# zif_breakout.net
KiCad netlist of a schematic drawn in EAGLE
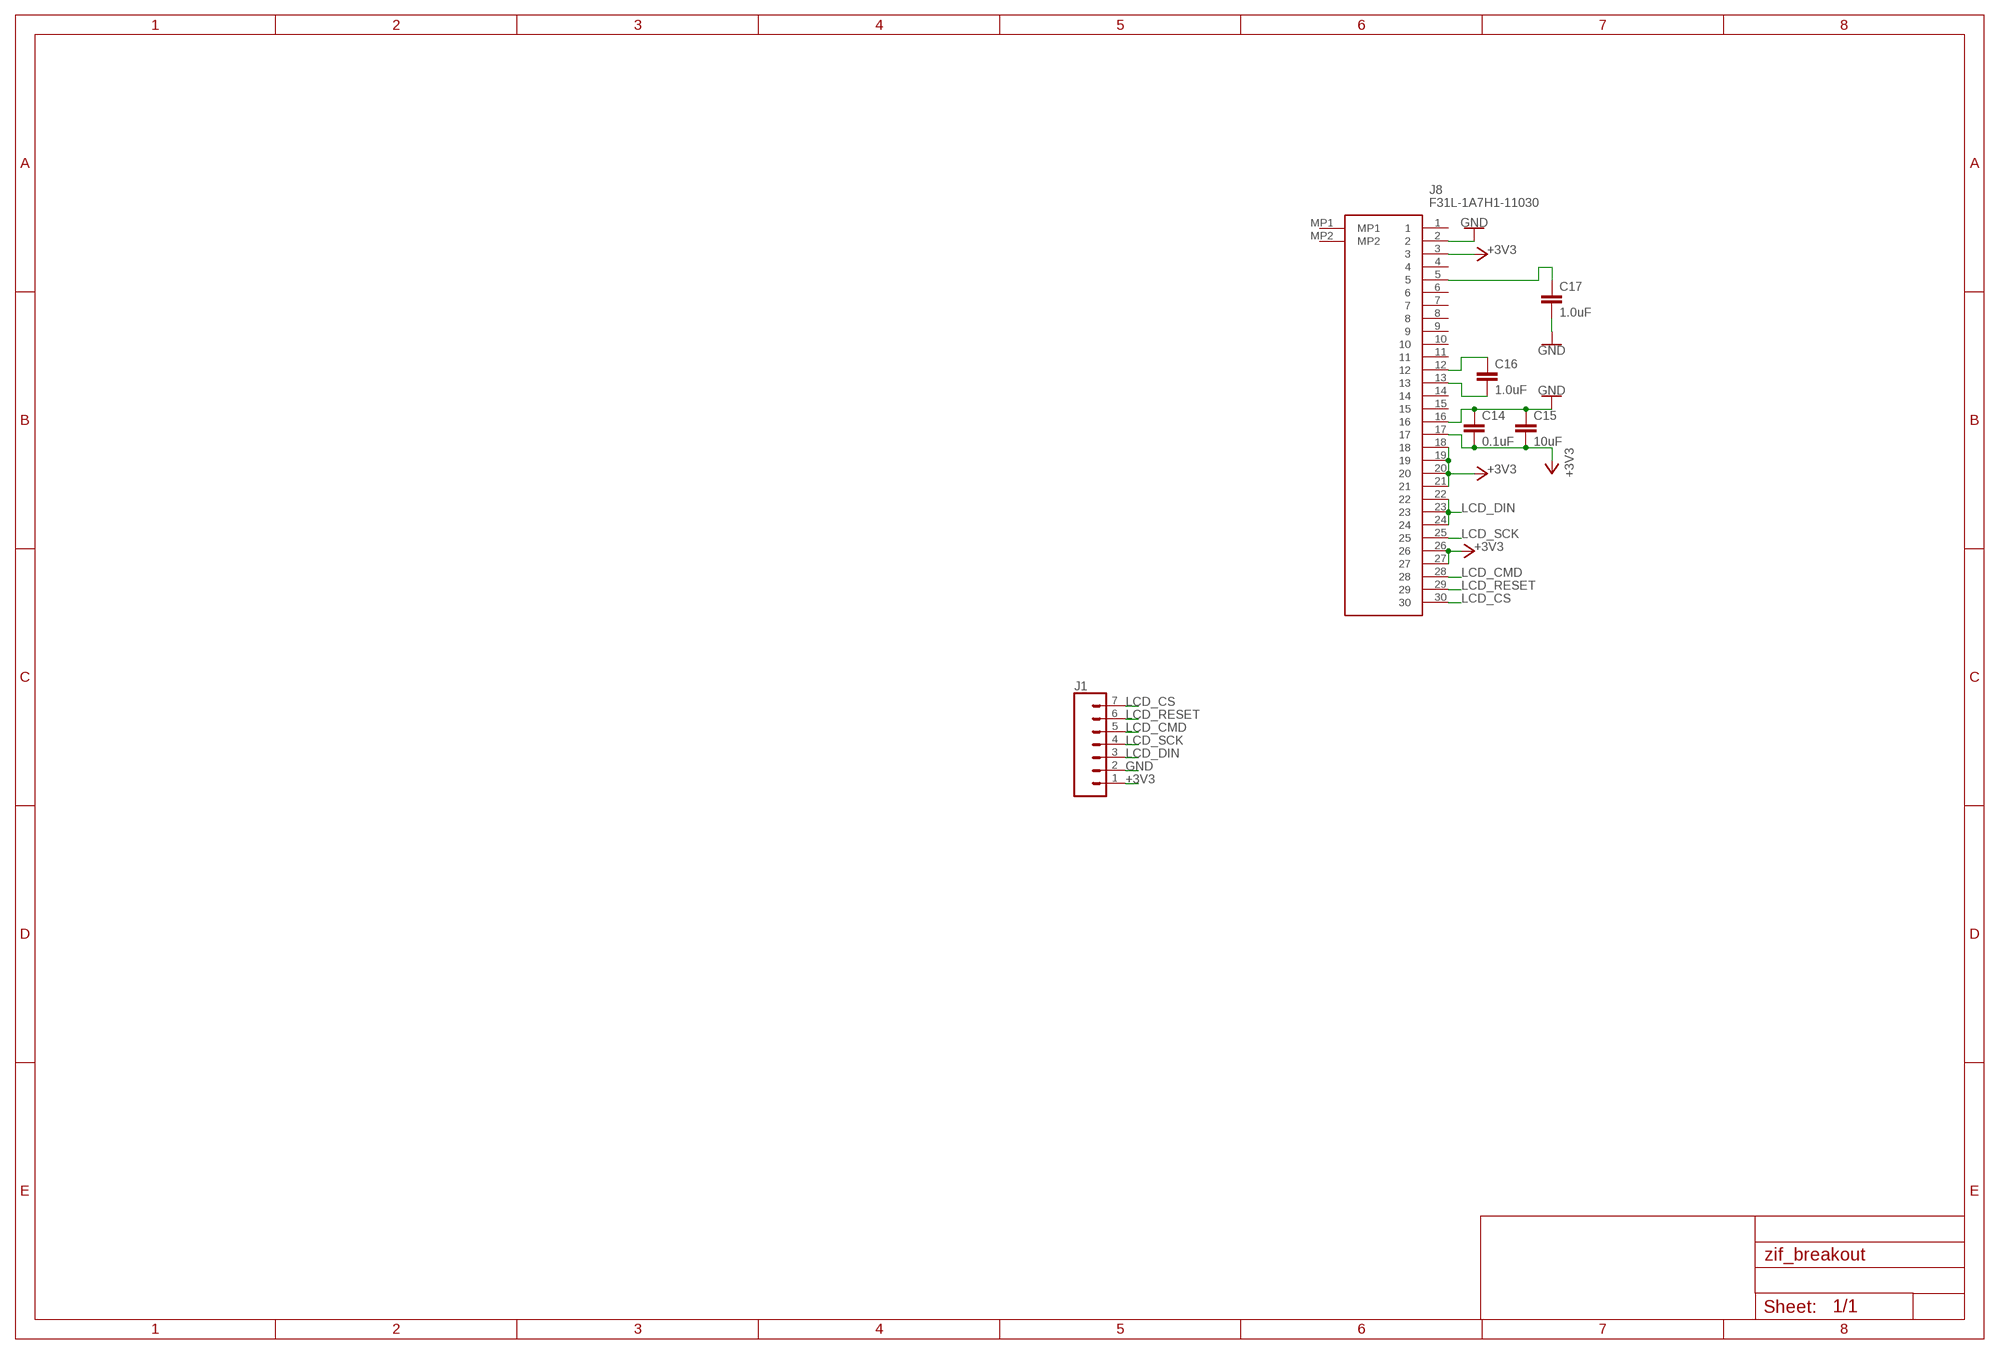
[diagram p0: schematic, sheet 1]

(export (version "E")
  (design (tool "Eeschema 10.0.6"))
  (components
    (comp (ref "C14")
      (value "0.1uF")
      (footprint "eagle-import:0603")
      (libsource (lib "eagle-import") (part "0.1UF-0603-25V-(+80/-20%)"))
    )
    (comp (ref "C15")
      (value "10uF")
      (footprint "eagle-import:0603")
      (libsource (lib "eagle-import") (part "10UF-0603-6.3V-20%"))
    )
    (comp (ref "C16")
      (value "1.0uF")
      (footprint "eagle-import:0603")
      (libsource (lib "eagle-import") (part "1.0UF-0603-16V-10%"))
    )
    (comp (ref "C17")
      (value "1.0uF")
      (footprint "eagle-import:0603")
      (libsource (lib "eagle-import") (part "1.0UF-0603-16V-10%"))
    )
    (comp (ref "J1")
      (value "CONN_07")
      (footprint "eagle-import:1X07")
      (libsource (lib "eagle-import") (part "CONN_07"))
    )
    (comp (ref "J8")
      (value "F31L-1A7H1-11030")
      (footprint "eagle-import:F31L1A7H111030")
      (fields (field (name "MOUSER_PART_NUMBER") "649-F31L-1A7H1-11030"))
      (libsource (lib "eagle-import") (part "F31L-1A7H1-11030"))
    )
  )
  (nets
    (net (code "1") (name "+3V3") (class "Default")
      (node (ref "C14") (pin "2") (pinfunction "2_2") (pintype "passive"))
      (node (ref "C15") (pin "2") (pinfunction "2_2") (pintype "passive"))
      (node (ref "J1") (pin "1") (pinfunction "1_1") (pintype "passive"))
      (node (ref "J8") (pin "17") (pinfunction "17_17") (pintype "bidirectional"))
      (node (ref "J8") (pin "18") (pinfunction "18_18") (pintype "bidirectional"))
      (node (ref "J8") (pin "19") (pinfunction "19_19") (pintype "bidirectional"))
      (node (ref "J8") (pin "20") (pinfunction "20_20") (pintype "bidirectional"))
      (node (ref "J8") (pin "21") (pinfunction "21_21") (pintype "bidirectional"))
      (node (ref "J8") (pin "26") (pinfunction "26_26") (pintype "bidirectional"))
      (node (ref "J8") (pin "27") (pinfunction "27_27") (pintype "bidirectional"))
      (node (ref "J8") (pin "3") (pinfunction "3_3") (pintype "bidirectional"))
    )
    (net (code "2") (name "/LCD_CMD") (class "Default")
      (node (ref "J1") (pin "5") (pinfunction "5_5") (pintype "passive"))
      (node (ref "J8") (pin "28") (pinfunction "28_28") (pintype "bidirectional"))
    )
    (net (code "3") (name "/LCD_CS") (class "Default")
      (node (ref "J1") (pin "7") (pinfunction "7_7") (pintype "passive"))
      (node (ref "J8") (pin "30") (pinfunction "30_30") (pintype "bidirectional"))
    )
    (net (code "4") (name "/LCD_DIN") (class "Default")
      (node (ref "J1") (pin "3") (pinfunction "3_3") (pintype "passive"))
      (node (ref "J8") (pin "22") (pinfunction "22_22") (pintype "bidirectional"))
      (node (ref "J8") (pin "23") (pinfunction "23_23") (pintype "bidirectional"))
      (node (ref "J8") (pin "24") (pinfunction "24_24") (pintype "bidirectional"))
    )
    (net (code "5") (name "/LCD_RESET") (class "Default")
      (node (ref "J1") (pin "6") (pinfunction "6_6") (pintype "passive"))
      (node (ref "J8") (pin "29") (pinfunction "29_29") (pintype "bidirectional"))
    )
    (net (code "6") (name "/LCD_SCK") (class "Default")
      (node (ref "J1") (pin "4") (pinfunction "4_4") (pintype "passive"))
      (node (ref "J8") (pin "25") (pinfunction "25_25") (pintype "bidirectional"))
    )
    (net (code "7") (name "GND") (class "Default")
      (node (ref "C14") (pin "1") (pinfunction "1_1") (pintype "passive"))
      (node (ref "C15") (pin "1") (pinfunction "1_1") (pintype "passive"))
      (node (ref "C17") (pin "2") (pinfunction "2_2") (pintype "passive"))
      (node (ref "J1") (pin "2") (pinfunction "2_2") (pintype "passive"))
      (node (ref "J8") (pin "16") (pinfunction "16_16") (pintype "bidirectional"))
      (node (ref "J8") (pin "2") (pinfunction "2_2") (pintype "bidirectional"))
    )
    (net (code "8") (name "Net-(C16-Pad1)") (class "Default")
      (node (ref "C16") (pin "1") (pinfunction "1_1") (pintype "passive"))
      (node (ref "J8") (pin "12") (pinfunction "12_12") (pintype "bidirectional"))
    )
    (net (code "9") (name "Net-(C16-Pad2)") (class "Default")
      (node (ref "C16") (pin "2") (pinfunction "2_2") (pintype "passive"))
      (node (ref "J8") (pin "13") (pinfunction "13_13") (pintype "bidirectional"))
    )
    (net (code "10") (name "Net-(C17-Pad1)") (class "Default")
      (node (ref "C17") (pin "1") (pinfunction "1_1") (pintype "passive"))
      (node (ref "J8") (pin "5") (pinfunction "5_5") (pintype "bidirectional"))
    )
    (net (code "11") (name "unconnected-(J8-Pad1)") (class "Default")
      (node (ref "J8") (pin "1") (pinfunction "1_1") (pintype "bidirectional"))
    )
    (net (code "12") (name "unconnected-(J8-Pad4)") (class "Default")
      (node (ref "J8") (pin "4") (pinfunction "4_4") (pintype "bidirectional"))
    )
    (net (code "13") (name "unconnected-(J8-Pad6)") (class "Default")
      (node (ref "J8") (pin "6") (pinfunction "6_6") (pintype "bidirectional"))
    )
    (net (code "14") (name "unconnected-(J8-Pad7)") (class "Default")
      (node (ref "J8") (pin "7") (pinfunction "7_7") (pintype "bidirectional"))
    )
    (net (code "15") (name "unconnected-(J8-Pad8)") (class "Default")
      (node (ref "J8") (pin "8") (pinfunction "8_8") (pintype "bidirectional"))
    )
    (net (code "16") (name "unconnected-(J8-Pad9)") (class "Default")
      (node (ref "J8") (pin "9") (pinfunction "9_9") (pintype "bidirectional"))
    )
    (net (code "17") (name "unconnected-(J8-Pad10)") (class "Default")
      (node (ref "J8") (pin "10") (pinfunction "10_10") (pintype "bidirectional"))
    )
    (net (code "18") (name "unconnected-(J8-Pad11)") (class "Default")
      (node (ref "J8") (pin "11") (pinfunction "11_11") (pintype "bidirectional"))
    )
    (net (code "19") (name "unconnected-(J8-Pad14)") (class "Default")
      (node (ref "J8") (pin "14") (pinfunction "14_14") (pintype "bidirectional"))
    )
    (net (code "20") (name "unconnected-(J8-Pad15)") (class "Default")
      (node (ref "J8") (pin "15") (pinfunction "15_15") (pintype "bidirectional"))
    )
    (net (code "21") (name "unconnected-(J8-PadMP1)") (class "Default")
      (node (ref "J8") (pin "MP1") (pinfunction "MP1_MP1") (pintype "bidirectional"))
    )
    (net (code "22") (name "unconnected-(J8-PadMP2)") (class "Default")
      (node (ref "J8") (pin "MP2") (pinfunction "MP2_MP2") (pintype "bidirectional"))
    )
  )
)
